# RPC_3V_Schematic.net
KiCad netlist of a schematic drawn in Altium Designer
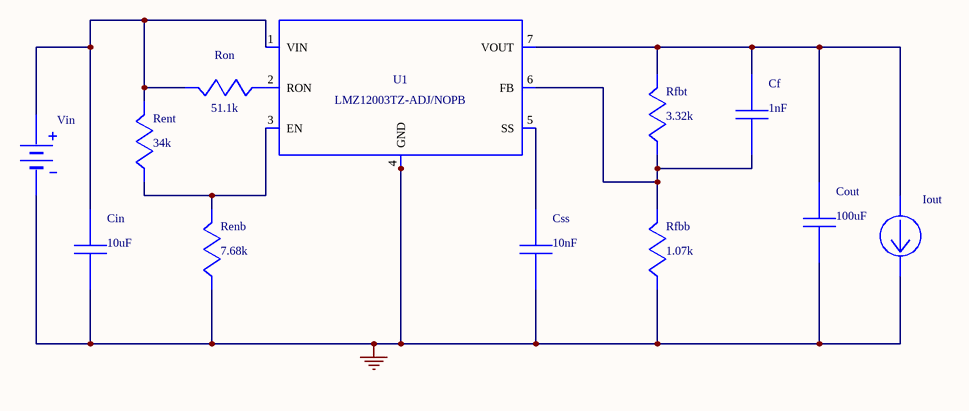
[diagram p0: RPC_3V_Schematic.schdoc]

(export (version "E")
  (design (tool "Eeschema 10.0.6"))
  (components
    (comp (ref "Cf")
      (value "1nF")
      (description "GRM1555C1H102JA0")
      (fields (field (name "MANUFACTURER PART NUMBER") "GRM1555C1H102JA01J"))
      (libsource (lib "TI WEBENCH") (part "Cf"))
    )
    (comp (ref "Cin")
      (value "10uF")
      (description "C2012X6S1C106K08")
      (fields (field (name "MANUFACTURER PART NUMBER") "C2012X6S1C106K085AC"))
      (libsource (lib "TI WEBENCH") (part "Cin"))
    )
    (comp (ref "Cout")
      (value "100uF")
      (description "GRM32EC80J107ME2")
      (fields (field (name "MANUFACTURER PART NUMBER") "GRM32EC80J107ME20L"))
      (libsource (lib "TI WEBENCH") (part "Cout"))
    )
    (comp (ref "Css")
      (value "10nF")
      (description "GRM216R71H103KA0")
      (fields (field (name "MANUFACTURER PART NUMBER") "GRM216R71H103KA01D"))
      (libsource (lib "TI WEBENCH") (part "Css"))
    )
    (comp (ref "Iout") (value "WB_CURRENT_LOAD") (libsource (lib "TI WEBENCH") (part "Iout")))
    (comp (ref "Renb")
      (value "7.68k")
      (description "ERJ-6ENF7681V")
      (libsource (lib "TI WEBENCH") (part "Renb"))
    )
    (comp (ref "Rent")
      (value "34k")
      (description "ERJ-6ENF3402V")
      (libsource (lib "TI WEBENCH") (part "Rent"))
    )
    (comp (ref "Rfbb")
      (value "1.07k")
      (description "ERJ-6ENF1071V")
      (libsource (lib "TI WEBENCH") (part "Rfbb"))
    )
    (comp (ref "Rfbt")
      (value "3.32k")
      (description "CRCW08053K32FKEA")
      (libsource (lib "TI WEBENCH") (part "Rfbt"))
    )
    (comp (ref "Ron")
      (value "51.1k")
      (description "ERJ-6ENF5112V")
      (libsource (lib "TI WEBENCH") (part "Ron"))
    )
    (comp (ref "U1")
      (value "LMZ12003TZ-ADJ/NOPB")
      (description "LMZ12003TZ-ADJ/N")
      (fields (field (name "PACKAGEREFERENCE") "LMZ12003TZ-ADJ/NOPB"))
      (libsource (lib "TI WEBENCH") (part "U1"))
    )
    (comp (ref "Vin") (value "WB_BATTERY") (libsource (lib "TI WEBENCH") (part "Vin")))
  )
  (nets
    (net (code "1") (name "0") (class "Default")
      (node (ref "Cin") (pin "2") (pinfunction "2_2") (pintype "passive"))
      (node (ref "Cout") (pin "2") (pinfunction "2_2") (pintype "passive"))
      (node (ref "Css") (pin "2") (pinfunction "2_2") (pintype "passive"))
      (node (ref "Iout") (pin "2") (pinfunction "-_2") (pintype "passive"))
      (node (ref "Renb") (pin "2") (pinfunction "2_2") (pintype "passive"))
      (node (ref "Rfbb") (pin "2") (pinfunction "2_2") (pintype "passive"))
      (node (ref "U1") (pin "4") (pinfunction "GND_4") (pintype "passive"))
      (node (ref "U1") (pin "8") (pinfunction "EP_8") (pintype "passive"))
      (node (ref "Vin") (pin "2") (pinfunction "-_2") (pintype "passive"))
    )
    (net (code "2") (name "Net-(Iout-+)") (class "Default")
      (node (ref "Cf") (pin "1") (pinfunction "1_1") (pintype "passive"))
      (node (ref "Cout") (pin "1") (pinfunction "1_1") (pintype "passive"))
      (node (ref "Iout") (pin "1") (pinfunction "+_1") (pintype "passive"))
      (node (ref "Rfbt") (pin "1") (pinfunction "1_1") (pintype "passive"))
      (node (ref "U1") (pin "7") (pinfunction "VOUT_7") (pintype "passive"))
    )
    (net (code "3") (name "Net-(U1-EN)") (class "Default")
      (node (ref "Renb") (pin "1") (pinfunction "1_1") (pintype "passive"))
      (node (ref "Rent") (pin "2") (pinfunction "2_2") (pintype "passive"))
      (node (ref "U1") (pin "3") (pinfunction "EN_3") (pintype "passive"))
    )
    (net (code "4") (name "Net-(U1-FB)") (class "Default")
      (node (ref "Cf") (pin "2") (pinfunction "2_2") (pintype "passive"))
      (node (ref "Rfbb") (pin "1") (pinfunction "1_1") (pintype "passive"))
      (node (ref "Rfbt") (pin "2") (pinfunction "2_2") (pintype "passive"))
      (node (ref "U1") (pin "6") (pinfunction "FB_6") (pintype "passive"))
    )
    (net (code "5") (name "Net-(U1-RON)") (class "Default")
      (node (ref "Ron") (pin "2") (pinfunction "2_2") (pintype "passive"))
      (node (ref "U1") (pin "2") (pinfunction "RON_2") (pintype "passive"))
    )
    (net (code "6") (name "Net-(U1-SS)") (class "Default")
      (node (ref "Css") (pin "1") (pinfunction "1_1") (pintype "passive"))
      (node (ref "U1") (pin "5") (pinfunction "SS_5") (pintype "passive"))
    )
    (net (code "7") (name "Net-(U1-VIN)") (class "Default")
      (node (ref "Cin") (pin "1") (pinfunction "1_1") (pintype "passive"))
      (node (ref "Rent") (pin "1") (pinfunction "1_1") (pintype "passive"))
      (node (ref "Ron") (pin "1") (pinfunction "1_1") (pintype "passive"))
      (node (ref "U1") (pin "1") (pinfunction "VIN_1") (pintype "passive"))
      (node (ref "Vin") (pin "1") (pinfunction "+_1") (pintype "passive"))
    )
  )
)
